# ft4222.net
KiCad netlist of a schematic drawn in Altium Designer
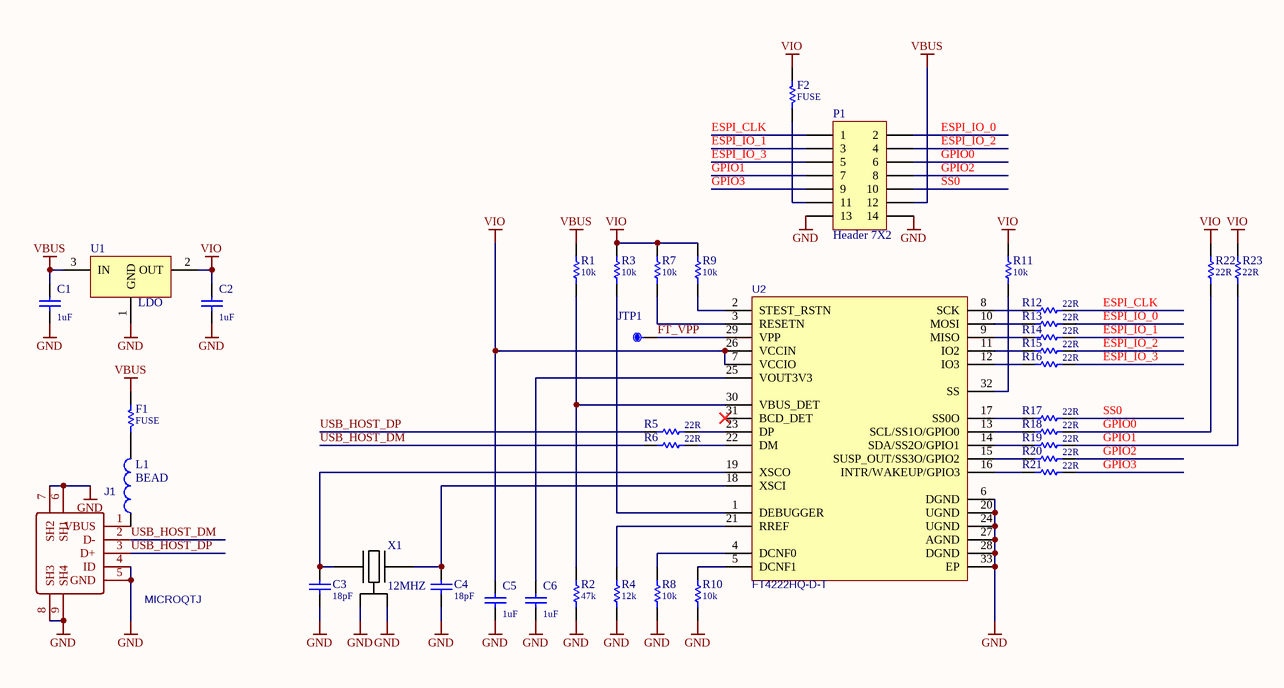
[diagram p0: ft4222.SchDoc]

(export (version "E")
  (design (tool "Eeschema 10.0.6"))
  (components
    (comp (ref "C1")
      (value "1uF")
      (footprint "C0603")
      (description "1uF 25V X7R 0603")
      (fields (field (name "LCSC PART NUMBER") "C59302"))
      (libsource (lib "Miscellaneous Devices") (part "CAP"))
    )
    (comp (ref "C2")
      (value "1uF")
      (footprint "C0603")
      (description "1uF 25V X7R 0603")
      (fields (field (name "LCSC PART NUMBER") "C59302"))
      (libsource (lib "Miscellaneous Devices") (part "CAP"))
    )
    (comp (ref "C3")
      (value "18pF")
      (footprint "C0402")
      (description "18pF 50V 0402")
      (fields (field (name "LCSC PART NUMBER") "C33149"))
      (libsource (lib "Miscellaneous Devices") (part "CAP"))
    )
    (comp (ref "C4")
      (value "18pF")
      (footprint "C0402")
      (description "18pF 50V 0402")
      (fields (field (name "LCSC PART NUMBER") "C33149"))
      (libsource (lib "Miscellaneous Devices") (part "CAP"))
    )
    (comp (ref "C5")
      (value "1uF")
      (footprint "C0603")
      (description "1uF 25V X7R 0603")
      (fields (field (name "LCSC PART NUMBER") "C59302"))
      (libsource (lib "Miscellaneous Devices") (part "CAP"))
    )
    (comp (ref "C6")
      (value "1uF")
      (footprint "C0603")
      (description "1uF 25V X7R 0603")
      (fields (field (name "LCSC PART NUMBER") "C59302"))
      (libsource (lib "Miscellaneous Devices") (part "CAP"))
    )
    (comp (ref "F1")
      (value "FUSE")
      (footprint "R1206")
      (libsource (lib "Miscellaneous Devices") (part "RES"))
    )
    (comp (ref "F2")
      (value "FUSE")
      (footprint "R1206")
      (libsource (lib "Miscellaneous Devices") (part "RES"))
    )
    (comp (ref "J1")
      (value "MICROQTJ")
      (footprint "MICRO-USB-SMD_MICROQTJ")
      (fields
        (field (name "BOM_SUPPLIER PART") "C404968")
        (field (name "BOM_MANUFACTURER PART") "MicroQTJ")
        (field (name "CONTRIBUTOR") "LCSC")
      )
      (libsource (lib "altium-import") (part "root_0_MICROQTJ_"))
    )
    (comp (ref "JTP1") (value "~") (footprint "TP30_SMD") (libsource (lib "*") (part "TP_Dup1")))
    (comp (ref "L1")
      (value "BEAD")
      (footprint "L0402")
      (description "INDUCTOR FERRITE BEAD 200mA 1 650mΩ 0402")
      (fields (field (name "LCSC PART NUMBER") "C92615"))
      (libsource (lib "Miscellaneous Devices") (part "BLM18AG601SN1D"))
    )
    (comp (ref "P1")
      (value "Header 7X2")
      (footprint "HDR2X7")
      (description "Header, 7-Pin, Dual row")
      (fields (field (name "PUBLISHER") "Altium Limited"))
      (libsource (lib "Miscellaneous Connectors") (part "Header 7X2"))
    )
    (comp (ref "R1")
      (value "10k")
      (footprint "R0603")
      (description "10k 0603")
      (libsource (lib "Miscellaneous Devices") (part "RES"))
    )
    (comp (ref "R2")
      (value "47k")
      (footprint "R0603")
      (description "47k 0603")
      (libsource (lib "Miscellaneous Devices") (part "RES"))
    )
    (comp (ref "R3")
      (value "10k")
      (footprint "R0603")
      (description "10k 0603")
      (libsource (lib "Miscellaneous Devices") (part "RES"))
    )
    (comp (ref "R4")
      (value "12k")
      (footprint "R0603")
      (description "12k 0603")
      (fields (field (name "LCSC PART NUMBER") "C114659"))
      (libsource (lib "Miscellaneous Devices") (part "RES"))
    )
    (comp (ref "R5")
      (value "22R")
      (footprint "R0603")
      (description "22R 5% 0603")
      (libsource (lib "Miscellaneous Devices") (part "RES"))
    )
    (comp (ref "R6")
      (value "22R")
      (footprint "R0603")
      (description "22R 5% 0603")
      (libsource (lib "Miscellaneous Devices") (part "RES"))
    )
    (comp (ref "R7")
      (value "10k")
      (footprint "R0603")
      (description "10k 0603")
      (libsource (lib "Miscellaneous Devices") (part "RES"))
    )
    (comp (ref "R8")
      (value "10k")
      (footprint "R0603")
      (description "10k 0603")
      (libsource (lib "Miscellaneous Devices") (part "RES"))
    )
    (comp (ref "R9")
      (value "10k")
      (footprint "R0603")
      (description "10k 0603")
      (libsource (lib "Miscellaneous Devices") (part "RES"))
    )
    (comp (ref "R10")
      (value "10k")
      (footprint "R0603")
      (description "10k 0603")
      (libsource (lib "Miscellaneous Devices") (part "RES"))
    )
    (comp (ref "R11")
      (value "10k")
      (footprint "R0603")
      (description "10k 0603")
      (libsource (lib "Miscellaneous Devices") (part "RES"))
    )
    (comp (ref "R12")
      (value "22R")
      (footprint "R0603")
      (description "22R 5% 0603")
      (libsource (lib "Miscellaneous Devices") (part "RES"))
    )
    (comp (ref "R13")
      (value "22R")
      (footprint "R0603")
      (description "22R 5% 0603")
      (libsource (lib "Miscellaneous Devices") (part "RES"))
    )
    (comp (ref "R14")
      (value "22R")
      (footprint "R0603")
      (description "22R 5% 0603")
      (libsource (lib "Miscellaneous Devices") (part "RES"))
    )
    (comp (ref "R15")
      (value "22R")
      (footprint "R0603")
      (description "22R 5% 0603")
      (libsource (lib "Miscellaneous Devices") (part "RES"))
    )
    (comp (ref "R16")
      (value "22R")
      (footprint "R0603")
      (description "22R 5% 0603")
      (libsource (lib "Miscellaneous Devices") (part "RES"))
    )
    (comp (ref "R17")
      (value "22R")
      (footprint "R0603")
      (description "22R 5% 0603")
      (libsource (lib "Miscellaneous Devices") (part "RES"))
    )
    (comp (ref "R18")
      (value "22R")
      (footprint "R0603")
      (description "22R 5% 0603")
      (libsource (lib "Miscellaneous Devices") (part "RES"))
    )
    (comp (ref "R19")
      (value "22R")
      (footprint "R0603")
      (description "22R 5% 0603")
      (libsource (lib "Miscellaneous Devices") (part "RES"))
    )
    (comp (ref "R20")
      (value "22R")
      (footprint "R0603")
      (description "22R 5% 0603")
      (libsource (lib "Miscellaneous Devices") (part "RES"))
    )
    (comp (ref "R21")
      (value "22R")
      (footprint "R0603")
      (description "22R 5% 0603")
      (libsource (lib "Miscellaneous Devices") (part "RES"))
    )
    (comp (ref "R22")
      (value "22R")
      (footprint "R0603")
      (description "22R 5% 0603")
      (libsource (lib "Miscellaneous Devices") (part "RES"))
    )
    (comp (ref "R23")
      (value "22R")
      (footprint "R0603")
      (description "22R 5% 0603")
      (libsource (lib "Miscellaneous Devices") (part "RES"))
    )
    (comp (ref "U1")
      (value "LDO")
      (footprint "TO-252AA (DPAK)")
      (libsource (lib "Miscellaneous Devices") (part "NCP51460SN33T1G"))
    )
    (comp (ref "U2")
      (value "FT4222HQ-D-T")
      (footprint "QFN-32_L5.0-W5.0-P0.50-BL-EP3.7")
      (fields (field (name "BOM_SUPPLIER PART") "C910592") (field (name "CONTRIBUTOR") "lcsc"))
      (libsource (lib "Schlib1") (part "FT4222HQ-D-T"))
    )
    (comp (ref "X1")
      (value "12MHZ")
      (footprint "CRYSTAL_3.2x2.5mm")
      (description "CRYSTAL 12MHZ 10PF SMD")
      (fields (field (name "LCSC PART NUMBER") "C70565"))
      (libsource (lib "Miscellaneous Devices") (part "CRYSTAL 12MHZ 3.20mm x 2.50mm"))
    )
  )
  (nets
    (net (code "1") (name "/ESPI_CLK") (class "Default")
      (node (ref "P1") (pin "1") (pinfunction "1_1") (pintype "passive"))
      (node (ref "R12") (pin "1") (pinfunction "1_1") (pintype "passive"))
    )
    (net (code "2") (name "/ESPI_IO_0") (class "Default")
      (node (ref "P1") (pin "2") (pinfunction "2_2") (pintype "passive"))
      (node (ref "R13") (pin "1") (pinfunction "1_1") (pintype "passive"))
    )
    (net (code "3") (name "/ESPI_IO_1") (class "Default")
      (node (ref "P1") (pin "3") (pinfunction "3_3") (pintype "passive"))
      (node (ref "R14") (pin "1") (pinfunction "1_1") (pintype "passive"))
    )
    (net (code "4") (name "/ESPI_IO_2") (class "Default")
      (node (ref "P1") (pin "4") (pinfunction "4_4") (pintype "passive"))
      (node (ref "R15") (pin "1") (pinfunction "1_1") (pintype "passive"))
    )
    (net (code "5") (name "/ESPI_IO_3") (class "Default")
      (node (ref "P1") (pin "5") (pinfunction "5_5") (pintype "passive"))
      (node (ref "R16") (pin "1") (pinfunction "1_1") (pintype "passive"))
    )
    (net (code "6") (name "/FT_VPP") (class "Default")
      (node (ref "JTP1") (pin "1") (pinfunction "1_1") (pintype "passive"))
      (node (ref "U2") (pin "29") (pinfunction "VPP_29") (pintype "passive"))
    )
    (net (code "7") (name "/GPIO0") (class "Default")
      (node (ref "P1") (pin "6") (pinfunction "6_6") (pintype "passive"))
      (node (ref "R18") (pin "1") (pinfunction "1_1") (pintype "passive"))
      (node (ref "R22") (pin "2") (pinfunction "2_2") (pintype "passive"))
    )
    (net (code "8") (name "/GPIO1") (class "Default")
      (node (ref "P1") (pin "7") (pinfunction "7_7") (pintype "passive"))
      (node (ref "R19") (pin "1") (pinfunction "1_1") (pintype "passive"))
      (node (ref "R23") (pin "2") (pinfunction "2_2") (pintype "passive"))
    )
    (net (code "9") (name "/GPIO2") (class "Default")
      (node (ref "P1") (pin "8") (pinfunction "8_8") (pintype "passive"))
      (node (ref "R20") (pin "1") (pinfunction "1_1") (pintype "passive"))
    )
    (net (code "10") (name "/GPIO3") (class "Default")
      (node (ref "P1") (pin "9") (pinfunction "9_9") (pintype "passive"))
      (node (ref "R21") (pin "1") (pinfunction "1_1") (pintype "passive"))
    )
    (net (code "11") (name "/SS0") (class "Default")
      (node (ref "P1") (pin "10") (pinfunction "10_10") (pintype "passive"))
      (node (ref "R17") (pin "1") (pinfunction "1_1") (pintype "passive"))
    )
    (net (code "12") (name "/USB_HOST_DM") (class "Default")
      (node (ref "J1") (pin "2") (pinfunction "D-_2") (pintype "passive"))
      (node (ref "R6") (pin "2") (pinfunction "2_2") (pintype "passive"))
    )
    (net (code "13") (name "/USB_HOST_DP") (class "Default")
      (node (ref "J1") (pin "3") (pinfunction "D+_3") (pintype "passive"))
      (node (ref "R5") (pin "2") (pinfunction "2_2") (pintype "passive"))
    )
    (net (code "14") (name "GND") (class "Default")
      (node (ref "C1") (pin "1") (pinfunction "1_1") (pintype "passive"))
      (node (ref "C2") (pin "1") (pinfunction "1_1") (pintype "passive"))
      (node (ref "C3") (pin "1") (pinfunction "1_1") (pintype "passive"))
      (node (ref "C4") (pin "1") (pinfunction "1_1") (pintype "passive"))
      (node (ref "C5") (pin "1") (pinfunction "1_1") (pintype "passive"))
      (node (ref "C6") (pin "1") (pinfunction "1_1") (pintype "passive"))
      (node (ref "J1") (pin "4") (pinfunction "ID_4") (pintype "passive"))
      (node (ref "J1") (pin "5") (pinfunction "GND_5") (pintype "passive"))
      (node (ref "J1") (pin "6") (pinfunction "SH1_6") (pintype "passive"))
      (node (ref "J1") (pin "7") (pinfunction "SH2_7") (pintype "passive"))
      (node (ref "J1") (pin "8") (pinfunction "SH3_8") (pintype "passive"))
      (node (ref "J1") (pin "9") (pinfunction "SH4_9") (pintype "passive"))
      (node (ref "P1") (pin "13") (pinfunction "13_13") (pintype "passive"))
      (node (ref "P1") (pin "14") (pinfunction "14_14") (pintype "passive"))
      (node (ref "R10") (pin "1") (pinfunction "1_1") (pintype "passive"))
      (node (ref "R2") (pin "1") (pinfunction "1_1") (pintype "passive"))
      (node (ref "R4") (pin "1") (pinfunction "1_1") (pintype "passive"))
      (node (ref "R8") (pin "1") (pinfunction "1_1") (pintype "passive"))
      (node (ref "U1") (pin "1") (pinfunction "GND_1") (pintype "passive"))
      (node (ref "U2") (pin "20") (pinfunction "UGND_20") (pintype "passive"))
      (node (ref "U2") (pin "24") (pinfunction "UGND_24") (pintype "passive"))
      (node (ref "U2") (pin "27") (pinfunction "AGND_27") (pintype "passive"))
      (node (ref "U2") (pin "28") (pinfunction "DGND_28") (pintype "passive"))
      (node (ref "U2") (pin "33") (pinfunction "EP_33") (pintype "passive"))
      (node (ref "U2") (pin "6") (pinfunction "DGND_6") (pintype "passive"))
      (node (ref "X1") (pin "2") (pinfunction "GND_2") (pintype "passive"))
      (node (ref "X1") (pin "4") (pinfunction "GND_4") (pintype "passive"))
    )
    (net (code "15") (name "Net-(F1-Pad1)") (class "Default")
      (node (ref "F1") (pin "1") (pinfunction "1_1") (pintype "passive"))
      (node (ref "L1") (pin "1") (pinfunction "1_1") (pintype "passive"))
    )
    (net (code "16") (name "Net-(F2-Pad1)") (class "Default")
      (node (ref "F2") (pin "1") (pinfunction "1_1") (pintype "passive"))
      (node (ref "P1") (pin "11") (pinfunction "11_11") (pintype "passive"))
    )
    (net (code "17") (name "Net-(J1-VBUS)") (class "Default")
      (node (ref "J1") (pin "1") (pinfunction "VBUS_1") (pintype "passive"))
      (node (ref "L1") (pin "2") (pinfunction "2_2") (pintype "passive"))
    )
    (net (code "18") (name "Net-(U2-DCNF0)") (class "Default")
      (node (ref "R8") (pin "2") (pinfunction "2_2") (pintype "passive"))
      (node (ref "U2") (pin "4") (pinfunction "DCNF0_4") (pintype "passive"))
    )
    (net (code "19") (name "Net-(U2-DCNF1)") (class "Default")
      (node (ref "R10") (pin "2") (pinfunction "2_2") (pintype "passive"))
      (node (ref "U2") (pin "5") (pinfunction "DCNF1_5") (pintype "passive"))
    )
    (net (code "20") (name "Net-(U2-DEBUGGER)") (class "Default")
      (node (ref "R3") (pin "1") (pinfunction "1_1") (pintype "passive"))
      (node (ref "U2") (pin "1") (pinfunction "DEBUGGER_1") (pintype "passive"))
    )
    (net (code "21") (name "Net-(U2-DM)") (class "Default")
      (node (ref "R6") (pin "1") (pinfunction "1_1") (pintype "passive"))
      (node (ref "U2") (pin "22") (pinfunction "DM_22") (pintype "passive"))
    )
    (net (code "22") (name "Net-(U2-DP)") (class "Default")
      (node (ref "R5") (pin "1") (pinfunction "1_1") (pintype "passive"))
      (node (ref "U2") (pin "23") (pinfunction "DP_23") (pintype "passive"))
    )
    (net (code "23") (name "Net-(U2-INTR{slash}WAKEUP{slash}GPIO3)") (class "Default")
      (node (ref "R21") (pin "2") (pinfunction "2_2") (pintype "passive"))
      (node (ref "U2") (pin "16") (pinfunction "INTR/WAKEUP/GPIO3_16") (pintype "passive"))
    )
    (net (code "24") (name "Net-(U2-IO2)") (class "Default")
      (node (ref "R15") (pin "2") (pinfunction "2_2") (pintype "passive"))
      (node (ref "U2") (pin "11") (pinfunction "IO2_11") (pintype "passive"))
    )
    (net (code "25") (name "Net-(U2-IO3)") (class "Default")
      (node (ref "R16") (pin "2") (pinfunction "2_2") (pintype "passive"))
      (node (ref "U2") (pin "12") (pinfunction "IO3_12") (pintype "passive"))
    )
    (net (code "26") (name "Net-(U2-MISO)") (class "Default")
      (node (ref "R14") (pin "2") (pinfunction "2_2") (pintype "passive"))
      (node (ref "U2") (pin "9") (pinfunction "MISO_9") (pintype "passive"))
    )
    (net (code "27") (name "Net-(U2-MOSI)") (class "Default")
      (node (ref "R13") (pin "2") (pinfunction "2_2") (pintype "passive"))
      (node (ref "U2") (pin "10") (pinfunction "MOSI_10") (pintype "passive"))
    )
    (net (code "28") (name "Net-(U2-RESETN)") (class "Default")
      (node (ref "R7") (pin "1") (pinfunction "1_1") (pintype "passive"))
      (node (ref "U2") (pin "3") (pinfunction "RESETN_3") (pintype "passive"))
    )
    (net (code "29") (name "Net-(U2-RREF)") (class "Default")
      (node (ref "R4") (pin "2") (pinfunction "2_2") (pintype "passive"))
      (node (ref "U2") (pin "21") (pinfunction "RREF_21") (pintype "passive"))
    )
    (net (code "30") (name "Net-(U2-SCK)") (class "Default")
      (node (ref "R12") (pin "2") (pinfunction "2_2") (pintype "passive"))
      (node (ref "U2") (pin "8") (pinfunction "SCK_8") (pintype "passive"))
    )
    (net (code "31") (name "Net-(U2-SCL{slash}SS1O{slash}GPIO0)") (class "Default")
      (node (ref "R18") (pin "2") (pinfunction "2_2") (pintype "passive"))
      (node (ref "U2") (pin "13") (pinfunction "SCL/SS1O/GPIO0_13") (pintype "passive"))
    )
    (net (code "32") (name "Net-(U2-SDA{slash}SS2O{slash}GPIO1)") (class "Default")
      (node (ref "R19") (pin "2") (pinfunction "2_2") (pintype "passive"))
      (node (ref "U2") (pin "14") (pinfunction "SDA/SS2O/GPIO1_14") (pintype "passive"))
    )
    (net (code "33") (name "Net-(U2-SS)") (class "Default")
      (node (ref "R11") (pin "1") (pinfunction "1_1") (pintype "passive"))
      (node (ref "U2") (pin "32") (pinfunction "SS_32") (pintype "passive"))
    )
    (net (code "34") (name "Net-(U2-SS0O)") (class "Default")
      (node (ref "R17") (pin "2") (pinfunction "2_2") (pintype "passive"))
      (node (ref "U2") (pin "17") (pinfunction "SS0O_17") (pintype "passive"))
    )
    (net (code "35") (name "Net-(U2-STEST_RSTN)") (class "Default")
      (node (ref "R9") (pin "1") (pinfunction "1_1") (pintype "passive"))
      (node (ref "U2") (pin "2") (pinfunction "STEST_RSTN_2") (pintype "passive"))
    )
    (net (code "36") (name "Net-(U2-SUSP_OUT{slash}SS3O{slash}GPIO2)") (class "Default")
      (node (ref "R20") (pin "2") (pinfunction "2_2") (pintype "passive"))
      (node (ref "U2") (pin "15") (pinfunction "SUSP_OUT/SS3O/GPIO2_15") (pintype "passive"))
    )
    (net (code "37") (name "Net-(U2-VBUS_DET)") (class "Default")
      (node (ref "R1") (pin "1") (pinfunction "1_1") (pintype "passive"))
      (node (ref "R2") (pin "2") (pinfunction "2_2") (pintype "passive"))
      (node (ref "U2") (pin "30") (pinfunction "VBUS_DET_30") (pintype "passive"))
    )
    (net (code "38") (name "Net-(U2-VOUT3V3)") (class "Default")
      (node (ref "C6") (pin "2") (pinfunction "2_2") (pintype "passive"))
      (node (ref "U2") (pin "25") (pinfunction "VOUT3V3_25") (pintype "passive"))
    )
    (net (code "39") (name "Net-(U2-XSCI)") (class "Default")
      (node (ref "C4") (pin "2") (pinfunction "2_2") (pintype "passive"))
      (node (ref "U2") (pin "18") (pinfunction "XSCI_18") (pintype "passive"))
      (node (ref "X1") (pin "3") (pinfunction "X2_3") (pintype "passive"))
    )
    (net (code "40") (name "Net-(U2-XSCO)") (class "Default")
      (node (ref "C3") (pin "2") (pinfunction "2_2") (pintype "passive"))
      (node (ref "U2") (pin "19") (pinfunction "XSCO_19") (pintype "passive"))
      (node (ref "X1") (pin "1") (pinfunction "X1_1") (pintype "passive"))
    )
    (net (code "41") (name "VBUS") (class "Default")
      (node (ref "C1") (pin "2") (pinfunction "2_2") (pintype "passive"))
      (node (ref "F1") (pin "2") (pinfunction "2_2") (pintype "passive"))
      (node (ref "P1") (pin "12") (pinfunction "12_12") (pintype "passive"))
      (node (ref "R1") (pin "2") (pinfunction "2_2") (pintype "passive"))
      (node (ref "U1") (pin "3") (pinfunction "IN_3") (pintype "passive"))
    )
    (net (code "42") (name "VIO") (class "Default")
      (node (ref "C2") (pin "2") (pinfunction "2_2") (pintype "passive"))
      (node (ref "C5") (pin "2") (pinfunction "2_2") (pintype "passive"))
      (node (ref "F2") (pin "2") (pinfunction "2_2") (pintype "passive"))
      (node (ref "R11") (pin "2") (pinfunction "2_2") (pintype "passive"))
      (node (ref "R22") (pin "1") (pinfunction "1_1") (pintype "passive"))
      (node (ref "R23") (pin "1") (pinfunction "1_1") (pintype "passive"))
      (node (ref "R3") (pin "2") (pinfunction "2_2") (pintype "passive"))
      (node (ref "R7") (pin "2") (pinfunction "2_2") (pintype "passive"))
      (node (ref "R9") (pin "2") (pinfunction "2_2") (pintype "passive"))
      (node (ref "U1") (pin "2") (pinfunction "OUT_2") (pintype "passive"))
      (node (ref "U2") (pin "26") (pinfunction "VCCIN_26") (pintype "passive"))
      (node (ref "U2") (pin "7") (pinfunction "VCCIO_7") (pintype "passive"))
    )
    (net (code "43") (name "unconnected-(U2-BCD_DET-Pad31)") (class "Default")
      (node (ref "U2") (pin "31") (pinfunction "BCD_DET_31") (pintype "passive+no_connect"))
    )
  )
)
